# combined-board.net
KiCad netlist of a schematic drawn in EAGLE
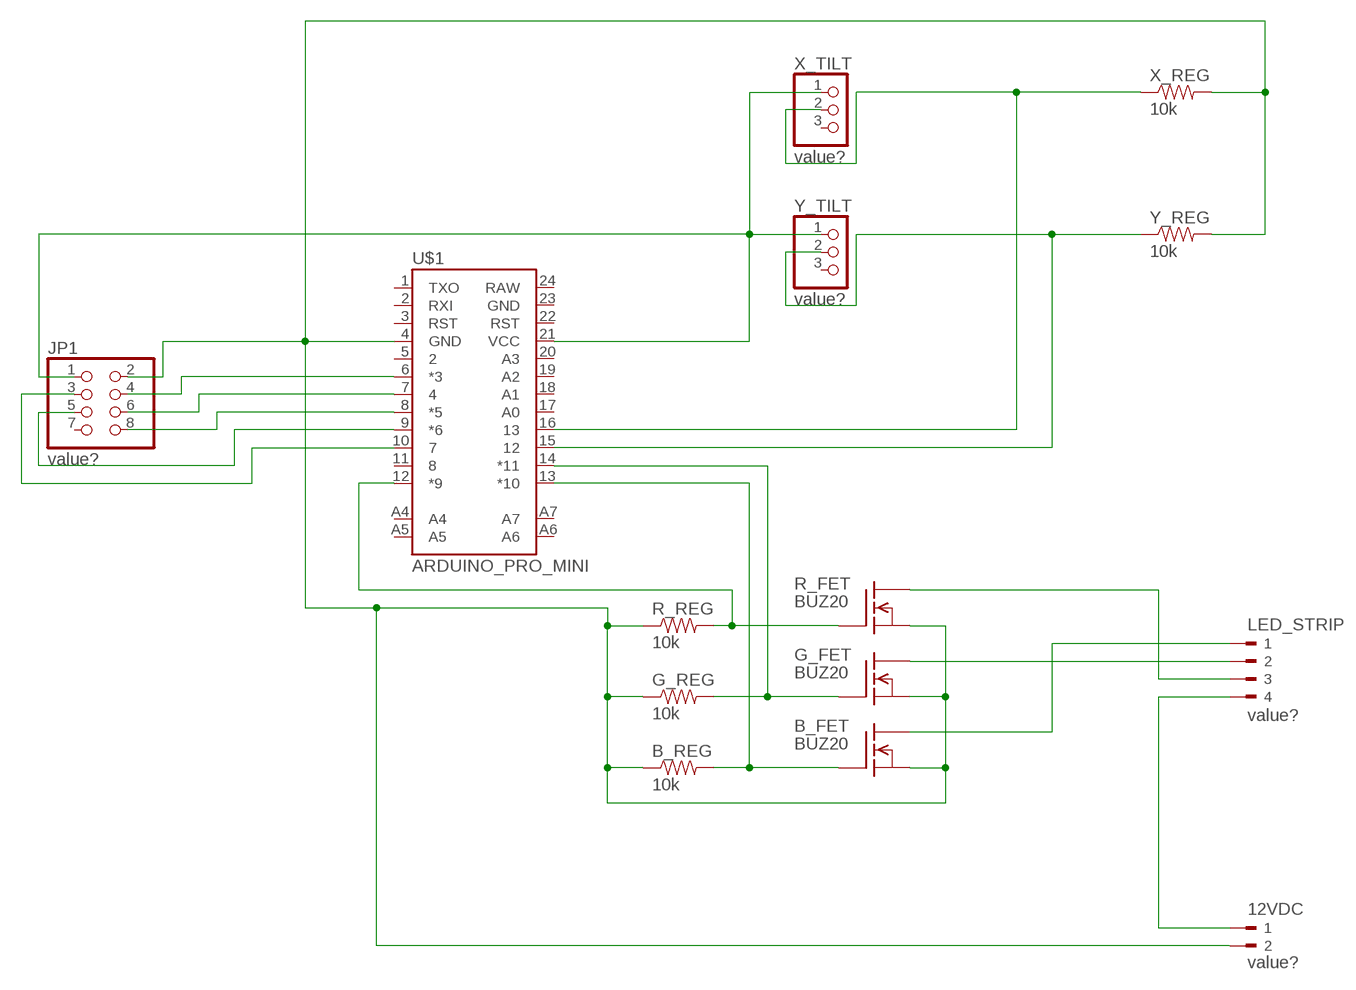
[diagram p0: schematic, sheet 1]

(export (version "E")
  (design (tool "Eeschema 10.0.6"))
  (components
    (comp (ref "12VDC")
      (value "value?")
      (footprint "eagle-import:180-2")
      (libsource (lib "eagle-import") (part "180-2"))
    )
    (comp (ref "B_FET")
      (value "BUZ20")
      (footprint "eagle-import:TO220")
      (libsource (lib "eagle-import") (part "BUZ20"))
    )
    (comp (ref "B_REG")
      (value "10k")
      (footprint "eagle-import:AXIAL-0.4")
      (libsource (lib "eagle-import") (part "RESISTORPTH-1/4W"))
    )
    (comp (ref "G_FET")
      (value "BUZ20")
      (footprint "eagle-import:TO220")
      (libsource (lib "eagle-import") (part "BUZ20"))
    )
    (comp (ref "G_REG")
      (value "10k")
      (footprint "eagle-import:AXIAL-0.4")
      (libsource (lib "eagle-import") (part "RESISTORPTH-1/4W"))
    )
    (comp (ref "JP1")
      (value "value?")
      (footprint "eagle-import:2X04")
      (libsource (lib "eagle-import") (part "PINHD-2X4"))
    )
    (comp (ref "LED_STRIP")
      (value "value?")
      (footprint "eagle-import:180-4")
      (libsource (lib "eagle-import") (part "180-4"))
    )
    (comp (ref "R_FET")
      (value "BUZ20")
      (footprint "eagle-import:TO220")
      (libsource (lib "eagle-import") (part "BUZ20"))
    )
    (comp (ref "R_REG")
      (value "10k")
      (footprint "eagle-import:AXIAL-0.4")
      (libsource (lib "eagle-import") (part "RESISTORPTH-1/4W"))
    )
    (comp (ref "U$1")
      (value "ARDUINO_PRO_MINI")
      (footprint "eagle-import:ARDUINO_PRO_MINI")
      (libsource (lib "eagle-import") (part "ARDUINO_PRO_MINI"))
    )
    (comp (ref "X_REG")
      (value "10k")
      (footprint "eagle-import:AXIAL-0.4")
      (libsource (lib "eagle-import") (part "RESISTORPTH-1/4W"))
    )
    (comp (ref "X_TILT")
      (value "value?")
      (footprint "eagle-import:1X03")
      (libsource (lib "eagle-import") (part "PINHD-1X3"))
    )
    (comp (ref "Y_REG")
      (value "10k")
      (footprint "eagle-import:AXIAL-0.4")
      (libsource (lib "eagle-import") (part "RESISTORPTH-1/4W"))
    )
    (comp (ref "Y_TILT")
      (value "value?")
      (footprint "eagle-import:1X03")
      (libsource (lib "eagle-import") (part "PINHD-1X3"))
    )
  )
  (nets
    (net (code "1") (name "Net-(12VDC-Pad1)") (class "Default")
      (node (ref "12VDC") (pin "1") (pinfunction "1_1") (pintype "passive"))
      (node (ref "LED_STRIP") (pin "4") (pinfunction "4_4") (pintype "passive"))
    )
    (net (code "2") (name "Net-(B_FET-D)") (class "Default")
      (node (ref "B_FET") (pin "2") (pinfunction "D_2") (pintype "passive"))
      (node (ref "LED_STRIP") (pin "1") (pinfunction "1_1") (pintype "passive"))
    )
    (net (code "3") (name "Net-(B_FET-G)") (class "Default")
      (node (ref "B_FET") (pin "1") (pinfunction "G_1") (pintype "passive"))
      (node (ref "B_REG") (pin "P$2") (pinfunction "2_P$2") (pintype "passive"))
      (node (ref "U$1") (pin "13") (pinfunction "*10_13") (pintype "bidirectional"))
    )
    (net (code "4") (name "Net-(B_FET-S)") (class "Default")
      (node (ref "12VDC") (pin "2") (pinfunction "2_2") (pintype "passive"))
      (node (ref "B_FET") (pin "3") (pinfunction "S_3") (pintype "passive"))
      (node (ref "B_REG") (pin "P$1") (pinfunction "1_P$1") (pintype "passive"))
      (node (ref "G_FET") (pin "3") (pinfunction "S_3") (pintype "passive"))
      (node (ref "G_REG") (pin "P$1") (pinfunction "1_P$1") (pintype "passive"))
      (node (ref "JP1") (pin "2") (pinfunction "2_2") (pintype "passive"))
      (node (ref "R_FET") (pin "3") (pinfunction "S_3") (pintype "passive"))
      (node (ref "R_REG") (pin "P$1") (pinfunction "1_P$1") (pintype "passive"))
      (node (ref "U$1") (pin "4") (pinfunction "GND_4") (pintype "bidirectional"))
      (node (ref "X_REG") (pin "P$2") (pinfunction "2_P$2") (pintype "passive"))
      (node (ref "Y_REG") (pin "P$2") (pinfunction "2_P$2") (pintype "passive"))
    )
    (net (code "5") (name "Net-(G_FET-D)") (class "Default")
      (node (ref "G_FET") (pin "2") (pinfunction "D_2") (pintype "passive"))
      (node (ref "LED_STRIP") (pin "2") (pinfunction "2_2") (pintype "passive"))
    )
    (net (code "6") (name "Net-(G_FET-G)") (class "Default")
      (node (ref "G_FET") (pin "1") (pinfunction "G_1") (pintype "passive"))
      (node (ref "G_REG") (pin "P$2") (pinfunction "2_P$2") (pintype "passive"))
      (node (ref "U$1") (pin "14") (pinfunction "*11_14") (pintype "bidirectional"))
    )
    (net (code "7") (name "Net-(R_FET-D)") (class "Default")
      (node (ref "LED_STRIP") (pin "3") (pinfunction "3_3") (pintype "passive"))
      (node (ref "R_FET") (pin "2") (pinfunction "D_2") (pintype "passive"))
    )
    (net (code "8") (name "Net-(R_FET-G)") (class "Default")
      (node (ref "R_FET") (pin "1") (pinfunction "G_1") (pintype "passive"))
      (node (ref "R_REG") (pin "P$2") (pinfunction "2_P$2") (pintype "passive"))
      (node (ref "U$1") (pin "12") (pinfunction "*9_12") (pintype "bidirectional"))
    )
    (net (code "9") (name "Net-(U$1-*3)") (class "Default")
      (node (ref "JP1") (pin "4") (pinfunction "4_4") (pintype "passive"))
      (node (ref "U$1") (pin "6") (pinfunction "*3_6") (pintype "bidirectional"))
    )
    (net (code "10") (name "Net-(U$1-*5)") (class "Default")
      (node (ref "JP1") (pin "8") (pinfunction "8_8") (pintype "passive"))
      (node (ref "U$1") (pin "8") (pinfunction "*5_8") (pintype "bidirectional"))
    )
    (net (code "11") (name "Net-(U$1-*6)") (class "Default")
      (node (ref "JP1") (pin "5") (pinfunction "5_5") (pintype "passive"))
      (node (ref "U$1") (pin "9") (pinfunction "*6_9") (pintype "bidirectional"))
    )
    (net (code "12") (name "Net-(U$1-4)") (class "Default")
      (node (ref "JP1") (pin "6") (pinfunction "6_6") (pintype "passive"))
      (node (ref "U$1") (pin "7") (pinfunction "4_7") (pintype "bidirectional"))
    )
    (net (code "13") (name "Net-(U$1-7)") (class "Default")
      (node (ref "JP1") (pin "3") (pinfunction "3_3") (pintype "passive"))
      (node (ref "U$1") (pin "10") (pinfunction "7_10") (pintype "bidirectional"))
    )
    (net (code "14") (name "Net-(U$1-12)") (class "Default")
      (node (ref "U$1") (pin "15") (pinfunction "12_15") (pintype "bidirectional"))
      (node (ref "Y_REG") (pin "P$1") (pinfunction "1_P$1") (pintype "passive"))
      (node (ref "Y_TILT") (pin "2") (pinfunction "2_2") (pintype "passive"))
    )
    (net (code "15") (name "Net-(U$1-13)") (class "Default")
      (node (ref "U$1") (pin "16") (pinfunction "13_16") (pintype "bidirectional"))
      (node (ref "X_REG") (pin "P$1") (pinfunction "1_P$1") (pintype "passive"))
      (node (ref "X_TILT") (pin "2") (pinfunction "2_2") (pintype "passive"))
    )
    (net (code "16") (name "Net-(U$1-VCC)") (class "Default")
      (node (ref "JP1") (pin "1") (pinfunction "1_1") (pintype "passive"))
      (node (ref "U$1") (pin "21") (pinfunction "VCC_21") (pintype "bidirectional"))
      (node (ref "X_TILT") (pin "1") (pinfunction "1_1") (pintype "passive"))
      (node (ref "Y_TILT") (pin "1") (pinfunction "1_1") (pintype "passive"))
    )
    (net (code "17") (name "unconnected-(JP1-Pad7)") (class "Default")
      (node (ref "JP1") (pin "7") (pinfunction "7_7") (pintype "passive"))
    )
    (net (code "18") (name "unconnected-(U$1-2-Pad5)") (class "Default")
      (node (ref "U$1") (pin "5") (pinfunction "2_5") (pintype "bidirectional"))
    )
    (net (code "19") (name "unconnected-(U$1-8-Pad11)") (class "Default")
      (node (ref "U$1") (pin "11") (pinfunction "8_11") (pintype "bidirectional"))
    )
    (net (code "20") (name "unconnected-(U$1-A0-Pad17)") (class "Default")
      (node (ref "U$1") (pin "17") (pinfunction "A0_17") (pintype "bidirectional"))
    )
    (net (code "21") (name "unconnected-(U$1-A1-Pad18)") (class "Default")
      (node (ref "U$1") (pin "18") (pinfunction "A1_18") (pintype "bidirectional"))
    )
    (net (code "22") (name "unconnected-(U$1-A2-Pad19)") (class "Default")
      (node (ref "U$1") (pin "19") (pinfunction "A2_19") (pintype "bidirectional"))
    )
    (net (code "23") (name "unconnected-(U$1-A3-Pad20)") (class "Default")
      (node (ref "U$1") (pin "20") (pinfunction "A3_20") (pintype "bidirectional"))
    )
    (net (code "24") (name "unconnected-(U$1-GND-Pad23)") (class "Default")
      (node (ref "U$1") (pin "23") (pinfunction "GND_23") (pintype "bidirectional"))
    )
    (net (code "25") (name "unconnected-(U$1-PadA4)") (class "Default")
      (node (ref "U$1") (pin "A4") (pinfunction "A4_A4") (pintype "bidirectional"))
    )
    (net (code "26") (name "unconnected-(U$1-PadA5)") (class "Default")
      (node (ref "U$1") (pin "A5") (pinfunction "A5_A5") (pintype "bidirectional"))
    )
    (net (code "27") (name "unconnected-(U$1-PadA6)") (class "Default")
      (node (ref "U$1") (pin "A6") (pinfunction "A6_A6") (pintype "bidirectional"))
    )
    (net (code "28") (name "unconnected-(U$1-PadA7)") (class "Default")
      (node (ref "U$1") (pin "A7") (pinfunction "A7_A7") (pintype "bidirectional"))
    )
    (net (code "29") (name "unconnected-(U$1-RAW-Pad24)") (class "Default")
      (node (ref "U$1") (pin "24") (pinfunction "RAW_24") (pintype "bidirectional"))
    )
    (net (code "30") (name "unconnected-(U$1-RST-Pad3)") (class "Default")
      (node (ref "U$1") (pin "3") (pinfunction "RST_3") (pintype "bidirectional"))
    )
    (net (code "31") (name "unconnected-(U$1-RST-Pad22)") (class "Default")
      (node (ref "U$1") (pin "22") (pinfunction "RST_22") (pintype "bidirectional"))
    )
    (net (code "32") (name "unconnected-(U$1-RXI-Pad2)") (class "Default")
      (node (ref "U$1") (pin "2") (pinfunction "RXI_2") (pintype "bidirectional"))
    )
    (net (code "33") (name "unconnected-(U$1-TXO-Pad1)") (class "Default")
      (node (ref "U$1") (pin "1") (pinfunction "TXO_1") (pintype "bidirectional"))
    )
    (net (code "34") (name "unconnected-(X_TILT-Pad3)") (class "Default")
      (node (ref "X_TILT") (pin "3") (pinfunction "3_3") (pintype "passive"))
    )
    (net (code "35") (name "unconnected-(Y_TILT-Pad3)") (class "Default")
      (node (ref "Y_TILT") (pin "3") (pinfunction "3_3") (pintype "passive"))
    )
  )
)
